# LCD.net
KiCad netlist of a schematic drawn in Altium Designer
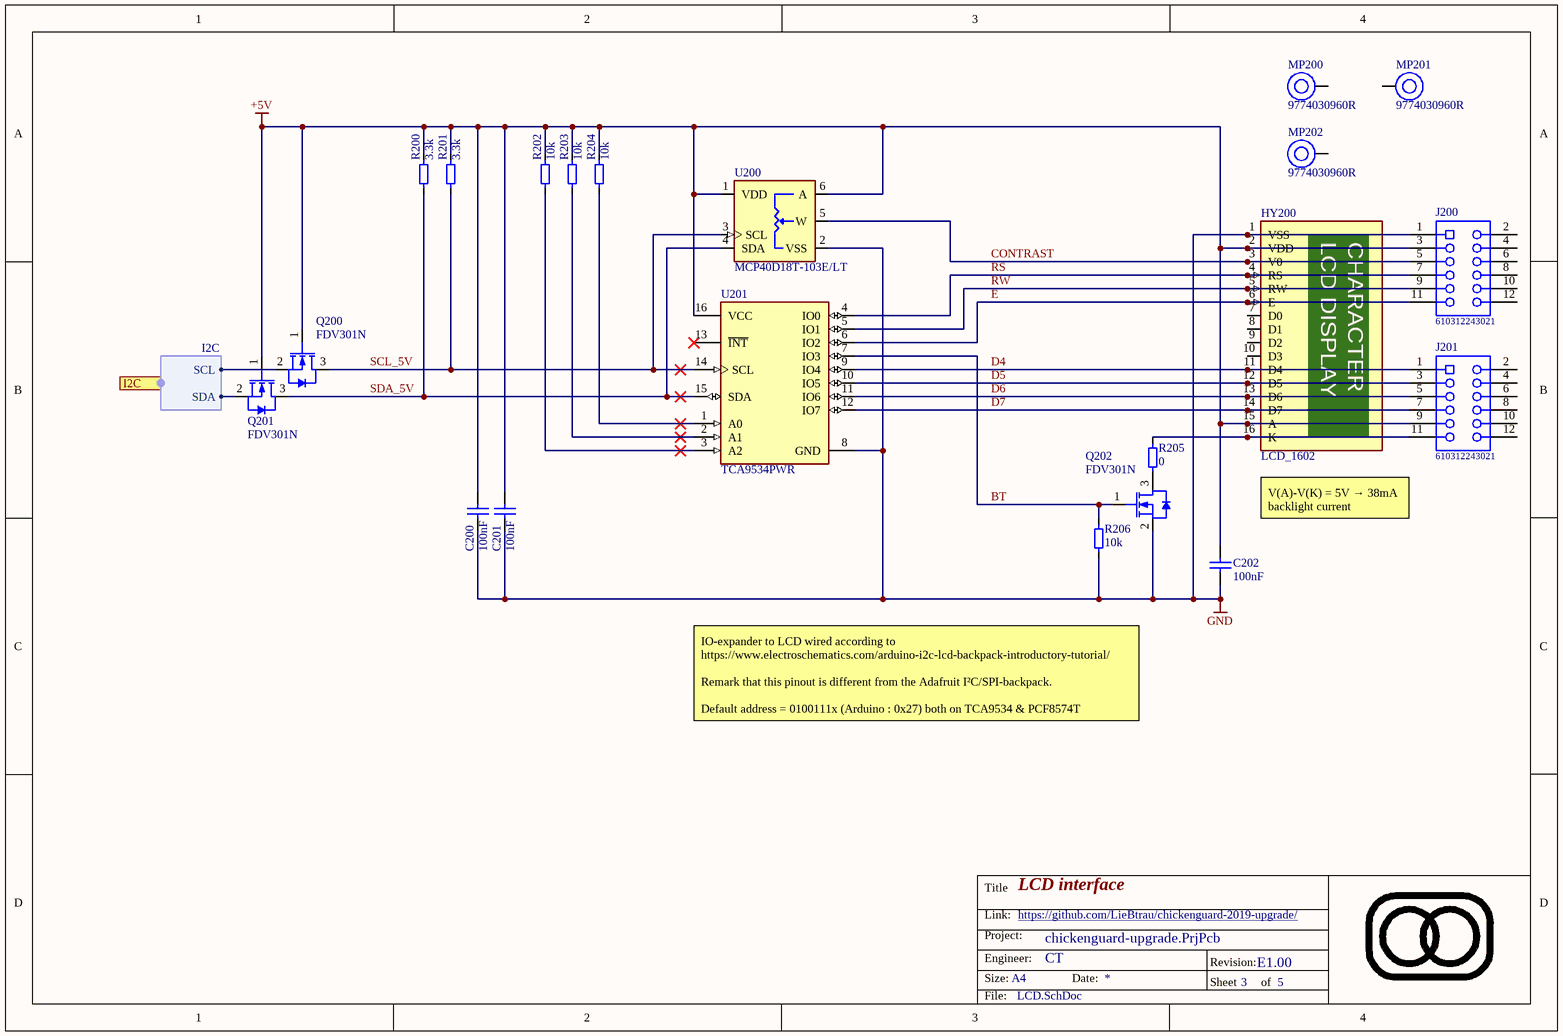
[diagram p0: LCD.SchDoc]

(export (version "E")
  (design (tool "Eeschema 10.0.6"))
  (components
    (comp (ref "C200")
      (value "100nF")
      (footprint "0603-C-N")
      (description "WCAP-CSGP Multilayer Ceramic Chip Capacitor, General Purpose, size 0603, X7R, 100nF, 10VDC")
      (fields (field (name "TOLERANCE") "10%") (field (name "Comment") "Capacitor 100nF +/-10% 10V X7R 0603"))
      (libsource (lib "7c7 Engineering") (part "CAP-NP-2"))
    )
    (comp (ref "C201")
      (value "100nF")
      (footprint "0603-C-N")
      (description "WCAP-CSGP Multilayer Ceramic Chip Capacitor, General Purpose, size 0603, X7R, 100nF, 10VDC")
      (fields (field (name "TOLERANCE") "10%") (field (name "Comment") "Capacitor 100nF +/-10% 10V X7R 0603"))
      (libsource (lib "7c7 Engineering") (part "CAP-NP-2"))
    )
    (comp (ref "C202")
      (value "100nF")
      (footprint "0603-C-N")
      (description "WCAP-CSGP Multilayer Ceramic Chip Capacitor, General Purpose, size 0603, X7R, 100nF, 10VDC")
      (fields (field (name "TOLERANCE") "10%") (field (name "Comment") "Capacitor 100nF +/-10% 10V X7R 0603"))
      (libsource (lib "7c7 Engineering") (part "CAP-NP-2"))
    )
    (comp (ref "HY200")
      (value "LCD_1602")
      (footprint "LCD_1602-BottomEntry")
      (description "2x16 character LCD display")
      (libsource (lib "7c7 Engineering") (part "CHAR_LCD_PARALLEL"))
    )
    (comp (ref "J200")
      (value "610312243021")
      (footprint "610312243021")
      (description "WR-PHD Socket Header, SMT, pitch 2.54mm, Dual Row, Vertical, 12p")
      (fields (field (name "MANUFACTURER") "Wurth Elektronik"))
      (libsource (lib "7c7 Engineering") (part "Symbol"))
    )
    (comp (ref "J201")
      (value "610312243021")
      (footprint "610312243021")
      (description "WR-PHD Socket Header, SMT, pitch 2.54mm, Dual Row, Vertical, 12p")
      (fields (field (name "MANUFACTURER") "Wurth Elektronik"))
      (libsource (lib "7c7 Engineering") (part "Symbol"))
    )
    (comp (ref "MP200")
      (value "9774030960R")
      (footprint "9774030960")
      (description "WA-SMST SMT Steel Spacer, OD 6mm, hole 3.3mm x 3mm")
      (fields (field (name "MANUFACTURER") "Wurth Elektronik"))
      (libsource (lib "7c7 Engineering") (part "9774160960R"))
    )
    (comp (ref "MP201")
      (value "9774030960R")
      (footprint "9774030960")
      (description "WA-SMST SMT Steel Spacer, OD 6mm, hole 3.3mm x 3mm")
      (fields (field (name "MANUFACTURER") "Wurth Elektronik"))
      (libsource (lib "7c7 Engineering") (part "9774160960R"))
    )
    (comp (ref "MP202")
      (value "9774030960R")
      (footprint "9774030960")
      (description "WA-SMST SMT Steel Spacer, OD 6mm, hole 3.3mm x 3mm")
      (fields (field (name "MANUFACTURER") "Wurth Elektronik"))
      (libsource (lib "7c7 Engineering") (part "9774160960R"))
    )
    (comp (ref "Q200")
      (value "FDV301N")
      (footprint "SOT-23-3-N")
      (description "Transistor MOSFET N-Ch. 25V 220mA 0, 35W 4Ohm SOT23")
      (libsource (lib "7c7 Engineering") (part "NEMOS-GSD-3"))
    )
    (comp (ref "Q201")
      (value "FDV301N")
      (footprint "SOT-23-3-N")
      (description "Transistor MOSFET N-Ch. 25V 220mA 0, 35W 4Ohm SOT23")
      (libsource (lib "7c7 Engineering") (part "NEMOS-GSD-3"))
    )
    (comp (ref "Q202")
      (value "FDV301N")
      (footprint "SOT-23-3-N")
      (description "Transistor MOSFET N-Ch. 25V 220mA 0, 35W 4Ohm SOT23")
      (libsource (lib "7c7 Engineering") (part "NEMOS-GSD-3"))
    )
    (comp (ref "R200")
      (value "3.3k")
      (footprint "0603-R-N")
      (description "Chip Resistor, Thick Film, General Purpose, 0603, 100mW, 75V, 3.3 kOhm, +/-1%")
      (fields (field (name "TOLERANCE") "1%") (field (name "JLCPCB PART #") "C22978"))
      (libsource (lib "7c7 Engineering") (part "RES"))
    )
    (comp (ref "R201")
      (value "3.3k")
      (footprint "0603-R-N")
      (description "Chip Resistor, Thick Film, General Purpose, 0603, 100mW, 75V, 3.3 kOhm, +/-1%")
      (fields (field (name "TOLERANCE") "1%") (field (name "JLCPCB PART #") "C22978"))
      (libsource (lib "7c7 Engineering") (part "RES"))
    )
    (comp (ref "R202")
      (value "10k")
      (footprint "0603-R-N")
      (description "Chip Resistor, Thin Film, Precision, 0603, 100mW, 75V, 10 kOhm, +/-0.05%")
      (fields (field (name "TOLERANCE") "0.05%") (field (name "Comment") "Resistor 10k +/-0.05% 75V 0603"))
      (libsource (lib "7c7 Engineering") (part "RES"))
    )
    (comp (ref "R203")
      (value "10k")
      (footprint "0603-R-N")
      (description "Chip Resistor, Thin Film, Precision, 0603, 100mW, 75V, 10 kOhm, +/-0.05%")
      (fields (field (name "TOLERANCE") "0.05%") (field (name "Comment") "Resistor 10k +/-0.05% 75V 0603"))
      (libsource (lib "7c7 Engineering") (part "RES"))
    )
    (comp (ref "R204")
      (value "10k")
      (footprint "0603-R-N")
      (description "Chip Resistor, Thin Film, Precision, 0603, 100mW, 75V, 10 kOhm, +/-0.05%")
      (fields (field (name "TOLERANCE") "0.05%") (field (name "Comment") "Resistor 10k +/-0.05% 75V 0603"))
      (libsource (lib "7c7 Engineering") (part "RES"))
    )
    (comp (ref "R205")
      (value "0")
      (footprint "1206-R-N")
      (description "Chip Jumper, Thick Film, Jumper, 1206, 250mW, 2A, 0 Ohm, <50 mOhm")
      (fields (field (name "TOLERANCE") "50 mOhm") (field (name "Comment") "Jumper 0R <50 mOhm 2A 1206"))
      (libsource (lib "7c7 Engineering") (part "RES"))
    )
    (comp (ref "R206")
      (value "10k")
      (footprint "0603-R-N")
      (description "Chip Resistor, Thin Film, Precision, 0603, 100mW, 75V, 10 kOhm, +/-0.05%")
      (fields (field (name "TOLERANCE") "0.05%") (field (name "Comment") "Resistor 10k +/-0.05% 75V 0603"))
      (libsource (lib "7c7 Engineering") (part "RES"))
    )
    (comp (ref "U200")
      (value "MCP40D18T-103E/LT")
      (footprint "SOT363-N")
      (description "Digital Potentiometer 10kOhm 128POS Volatile Linear Automotive 6-Pin SC-70 T/R")
      (fields (field (name "TOLERANCE") "20%"))
      (libsource (lib "7c7 Engineering") (part "IN-DPOT-MCP4018-6"))
    )
    (comp (ref "U201")
      (value "TCA9534PWR")
      (footprint "TSSOP16-0.65-4.4-L")
      (description "8-bit I/O expander, I2C/SMBus, 400kHz, 1.65 to 5.5V, TSSOP-16")
      (libsource (lib "7c7 Engineering") (part "04628dd91dbb09866b58f3fb2ae999f"))
    )
  )
  (nets
    (net (code "2") (name "+5V") (class "Default")
      (node (ref "C200") (pin "2") (pinfunction "2_2") (pintype "passive"))
      (node (ref "C201") (pin "2") (pinfunction "2_2") (pintype "passive"))
      (node (ref "C202") (pin "2") (pinfunction "2_2") (pintype "passive"))
      (node (ref "HY200") (pin "15") (pinfunction "A_15") (pintype "power_in"))
      (node (ref "HY200") (pin "2") (pinfunction "VDD_2") (pintype "power_in"))
      (node (ref "J200") (pin "3") (pinfunction "3_3") (pintype "passive"))
      (node (ref "J201") (pin "9") (pinfunction "9_9") (pintype "passive"))
      (node (ref "Q200") (pin "1") (pinfunction "G_1") (pintype "passive"))
      (node (ref "Q201") (pin "1") (pinfunction "G_1") (pintype "passive"))
      (node (ref "R200") (pin "2") (pinfunction "2_2") (pintype "passive"))
      (node (ref "R201") (pin "2") (pinfunction "2_2") (pintype "passive"))
      (node (ref "R202") (pin "2") (pinfunction "2_2") (pintype "passive"))
      (node (ref "R203") (pin "2") (pinfunction "2_2") (pintype "passive"))
      (node (ref "R204") (pin "2") (pinfunction "2_2") (pintype "passive"))
      (node (ref "U200") (pin "1") (pinfunction "VDD_1") (pintype "power_in"))
      (node (ref "U200") (pin "6") (pinfunction "A_6") (pintype "passive"))
      (node (ref "U201") (pin "16") (pinfunction "VCC_16") (pintype "power_in"))
    )
    (net (code "3") (name "/BT") (class "Default")
      (node (ref "Q202") (pin "1") (pinfunction "G_1") (pintype "passive"))
      (node (ref "R206") (pin "2") (pinfunction "2_2") (pintype "passive"))
      (node (ref "U201") (pin "7") (pinfunction "IO3_7") (pintype "bidirectional"))
    )
    (net (code "4") (name "/CONTRAST") (class "Default")
      (node (ref "HY200") (pin "3") (pinfunction "V0_3") (pintype "power_in"))
      (node (ref "J200") (pin "5") (pinfunction "5_5") (pintype "passive"))
      (node (ref "U200") (pin "5") (pinfunction "W_5") (pintype "passive"))
    )
    (net (code "5") (name "/D4") (class "Default")
      (node (ref "HY200") (pin "11") (pinfunction "D4_11") (pintype "bidirectional"))
      (node (ref "J201") (pin "1") (pinfunction "1_1") (pintype "passive"))
      (node (ref "U201") (pin "9") (pinfunction "IO4_9") (pintype "bidirectional"))
    )
    (net (code "6") (name "/D5") (class "Default")
      (node (ref "HY200") (pin "12") (pinfunction "D5_12") (pintype "bidirectional"))
      (node (ref "J201") (pin "3") (pinfunction "3_3") (pintype "passive"))
      (node (ref "U201") (pin "10") (pinfunction "IO5_10") (pintype "bidirectional"))
    )
    (net (code "7") (name "/D6") (class "Default")
      (node (ref "HY200") (pin "13") (pinfunction "D6_13") (pintype "bidirectional"))
      (node (ref "J201") (pin "5") (pinfunction "5_5") (pintype "passive"))
      (node (ref "U201") (pin "11") (pinfunction "IO6_11") (pintype "bidirectional"))
    )
    (net (code "8") (name "/D7") (class "Default")
      (node (ref "HY200") (pin "14") (pinfunction "D7_14") (pintype "bidirectional"))
      (node (ref "J201") (pin "7") (pinfunction "7_7") (pintype "passive"))
      (node (ref "U201") (pin "12") (pinfunction "IO7_12") (pintype "bidirectional"))
    )
    (net (code "9") (name "/E") (class "Default")
      (node (ref "HY200") (pin "6") (pinfunction "E_6") (pintype "input"))
      (node (ref "J200") (pin "11") (pinfunction "11_11") (pintype "passive"))
      (node (ref "U201") (pin "6") (pinfunction "IO2_6") (pintype "bidirectional"))
    )
    (net (code "10") (name "/RS") (class "Default")
      (node (ref "HY200") (pin "4") (pinfunction "RS_4") (pintype "input"))
      (node (ref "J200") (pin "7") (pinfunction "7_7") (pintype "passive"))
      (node (ref "U201") (pin "4") (pinfunction "IO0_4") (pintype "bidirectional"))
    )
    (net (code "11") (name "/RW") (class "Default")
      (node (ref "HY200") (pin "5") (pinfunction "RW_5") (pintype "input"))
      (node (ref "J200") (pin "9") (pinfunction "9_9") (pintype "passive"))
      (node (ref "U201") (pin "5") (pinfunction "IO1_5") (pintype "bidirectional"))
    )
    (net (code "12") (name "/SCL") (class "Default")
      (node (ref "Q200") (pin "2") (pinfunction "S_2") (pintype "passive"))
    )
    (net (code "13") (name "/SCL_5V") (class "Default")
      (node (ref "Q200") (pin "3") (pinfunction "D_3") (pintype "passive"))
      (node (ref "R201") (pin "1") (pinfunction "1_1") (pintype "passive"))
      (node (ref "U200") (pin "3") (pinfunction "SCL_3") (pintype "input"))
      (node (ref "U201") (pin "14") (pinfunction "SCL_14") (pintype "input"))
    )
    (net (code "14") (name "/SDA") (class "Default")
      (node (ref "Q201") (pin "2") (pinfunction "S_2") (pintype "passive"))
    )
    (net (code "15") (name "/SDA_5V") (class "Default")
      (node (ref "Q201") (pin "3") (pinfunction "D_3") (pintype "passive"))
      (node (ref "R200") (pin "1") (pinfunction "1_1") (pintype "passive"))
      (node (ref "U200") (pin "4") (pinfunction "SDA_4") (pintype "bidirectional"))
      (node (ref "U201") (pin "15") (pinfunction "SDA_15") (pintype "bidirectional"))
    )
    (net (code "17") (name "GND") (class "Default")
      (node (ref "C200") (pin "1") (pinfunction "1_1") (pintype "passive"))
      (node (ref "C201") (pin "1") (pinfunction "1_1") (pintype "passive"))
      (node (ref "C202") (pin "1") (pinfunction "1_1") (pintype "passive"))
      (node (ref "HY200") (pin "1") (pinfunction "VSS_1") (pintype "power_in"))
      (node (ref "J200") (pin "1") (pinfunction "1_1") (pintype "passive"))
      (node (ref "Q202") (pin "2") (pinfunction "S_2") (pintype "passive"))
      (node (ref "R206") (pin "1") (pinfunction "1_1") (pintype "passive"))
      (node (ref "U200") (pin "2") (pinfunction "VSS_2") (pintype "power_in"))
      (node (ref "U201") (pin "8") (pinfunction "GND_8") (pintype "power_in"))
    )
    (net (code "18") (name "Net-(HY200-K)") (class "Default")
      (node (ref "HY200") (pin "16") (pinfunction "K_16") (pintype "power_in"))
      (node (ref "J201") (pin "11") (pinfunction "11_11") (pintype "passive"))
      (node (ref "R205") (pin "2") (pinfunction "2_2") (pintype "passive"))
    )
    (net (code "19") (name "Net-(Q202-D)") (class "Default")
      (node (ref "Q202") (pin "3") (pinfunction "D_3") (pintype "passive"))
      (node (ref "R205") (pin "1") (pinfunction "1_1") (pintype "passive"))
    )
    (net (code "20") (name "Net-(U201-A0)") (class "Default")
      (node (ref "R204") (pin "1") (pinfunction "1_1") (pintype "passive"))
      (node (ref "U201") (pin "1") (pinfunction "A0_1") (pintype "input"))
    )
    (net (code "21") (name "Net-(U201-A1)") (class "Default")
      (node (ref "R203") (pin "1") (pinfunction "1_1") (pintype "passive"))
      (node (ref "U201") (pin "2") (pinfunction "A1_2") (pintype "input"))
    )
    (net (code "22") (name "Net-(U201-A2)") (class "Default")
      (node (ref "R202") (pin "1") (pinfunction "1_1") (pintype "passive"))
      (node (ref "U201") (pin "3") (pinfunction "A2_3") (pintype "input"))
    )
    (net (code "23") (name "unconnected-(HY200-D0-Pad7)") (class "Default")
      (node (ref "HY200") (pin "7") (pinfunction "D0_7") (pintype "bidirectional"))
    )
    (net (code "24") (name "unconnected-(HY200-D1-Pad8)") (class "Default")
      (node (ref "HY200") (pin "8") (pinfunction "D1_8") (pintype "bidirectional"))
    )
    (net (code "25") (name "unconnected-(HY200-D2-Pad9)") (class "Default")
      (node (ref "HY200") (pin "9") (pinfunction "D2_9") (pintype "bidirectional"))
    )
    (net (code "26") (name "unconnected-(HY200-D3-Pad10)") (class "Default")
      (node (ref "HY200") (pin "10") (pinfunction "D3_10") (pintype "bidirectional"))
    )
    (net (code "27") (name "unconnected-(J200-Pad2)") (class "Default")
      (node (ref "J200") (pin "2") (pinfunction "2_2") (pintype "passive"))
    )
    (net (code "28") (name "unconnected-(J200-Pad4)") (class "Default")
      (node (ref "J200") (pin "4") (pinfunction "4_4") (pintype "passive"))
    )
    (net (code "29") (name "unconnected-(J200-Pad6)") (class "Default")
      (node (ref "J200") (pin "6") (pinfunction "6_6") (pintype "passive"))
    )
    (net (code "30") (name "unconnected-(J200-Pad8)") (class "Default")
      (node (ref "J200") (pin "8") (pinfunction "8_8") (pintype "passive"))
    )
    (net (code "31") (name "unconnected-(J200-Pad10)") (class "Default")
      (node (ref "J200") (pin "10") (pinfunction "10_10") (pintype "passive"))
    )
    (net (code "32") (name "unconnected-(J200-Pad12)") (class "Default")
      (node (ref "J200") (pin "12") (pinfunction "12_12") (pintype "passive"))
    )
    (net (code "33") (name "unconnected-(J201-Pad2)") (class "Default")
      (node (ref "J201") (pin "2") (pinfunction "2_2") (pintype "passive"))
    )
    (net (code "34") (name "unconnected-(J201-Pad4)") (class "Default")
      (node (ref "J201") (pin "4") (pinfunction "4_4") (pintype "passive"))
    )
    (net (code "35") (name "unconnected-(J201-Pad6)") (class "Default")
      (node (ref "J201") (pin "6") (pinfunction "6_6") (pintype "passive"))
    )
    (net (code "36") (name "unconnected-(J201-Pad8)") (class "Default")
      (node (ref "J201") (pin "8") (pinfunction "8_8") (pintype "passive"))
    )
    (net (code "37") (name "unconnected-(J201-Pad10)") (class "Default")
      (node (ref "J201") (pin "10") (pinfunction "10_10") (pintype "passive"))
    )
    (net (code "38") (name "unconnected-(J201-Pad12)") (class "Default")
      (node (ref "J201") (pin "12") (pinfunction "12_12") (pintype "passive"))
    )
    (net (code "39") (name "unconnected-(MP200-Pad1)") (class "Default")
      (node (ref "MP200") (pin "1") (pinfunction "1_1") (pintype "passive"))
    )
    (net (code "40") (name "unconnected-(MP201-Pad1)") (class "Default")
      (node (ref "MP201") (pin "1") (pinfunction "1_1") (pintype "passive"))
    )
    (net (code "41") (name "unconnected-(MP202-Pad1)") (class "Default")
      (node (ref "MP202") (pin "1") (pinfunction "1_1") (pintype "passive"))
    )
    (net (code "42") (name "unconnected-(U201-~{INT}-Pad13)") (class "Default")
      (node (ref "U201") (pin "13") (pinfunction "~{INT}_13") (pintype "open_collector+no_connect"))
    )
  )
)
